# MCU.net
KiCad netlist of a schematic drawn in Altium Designer
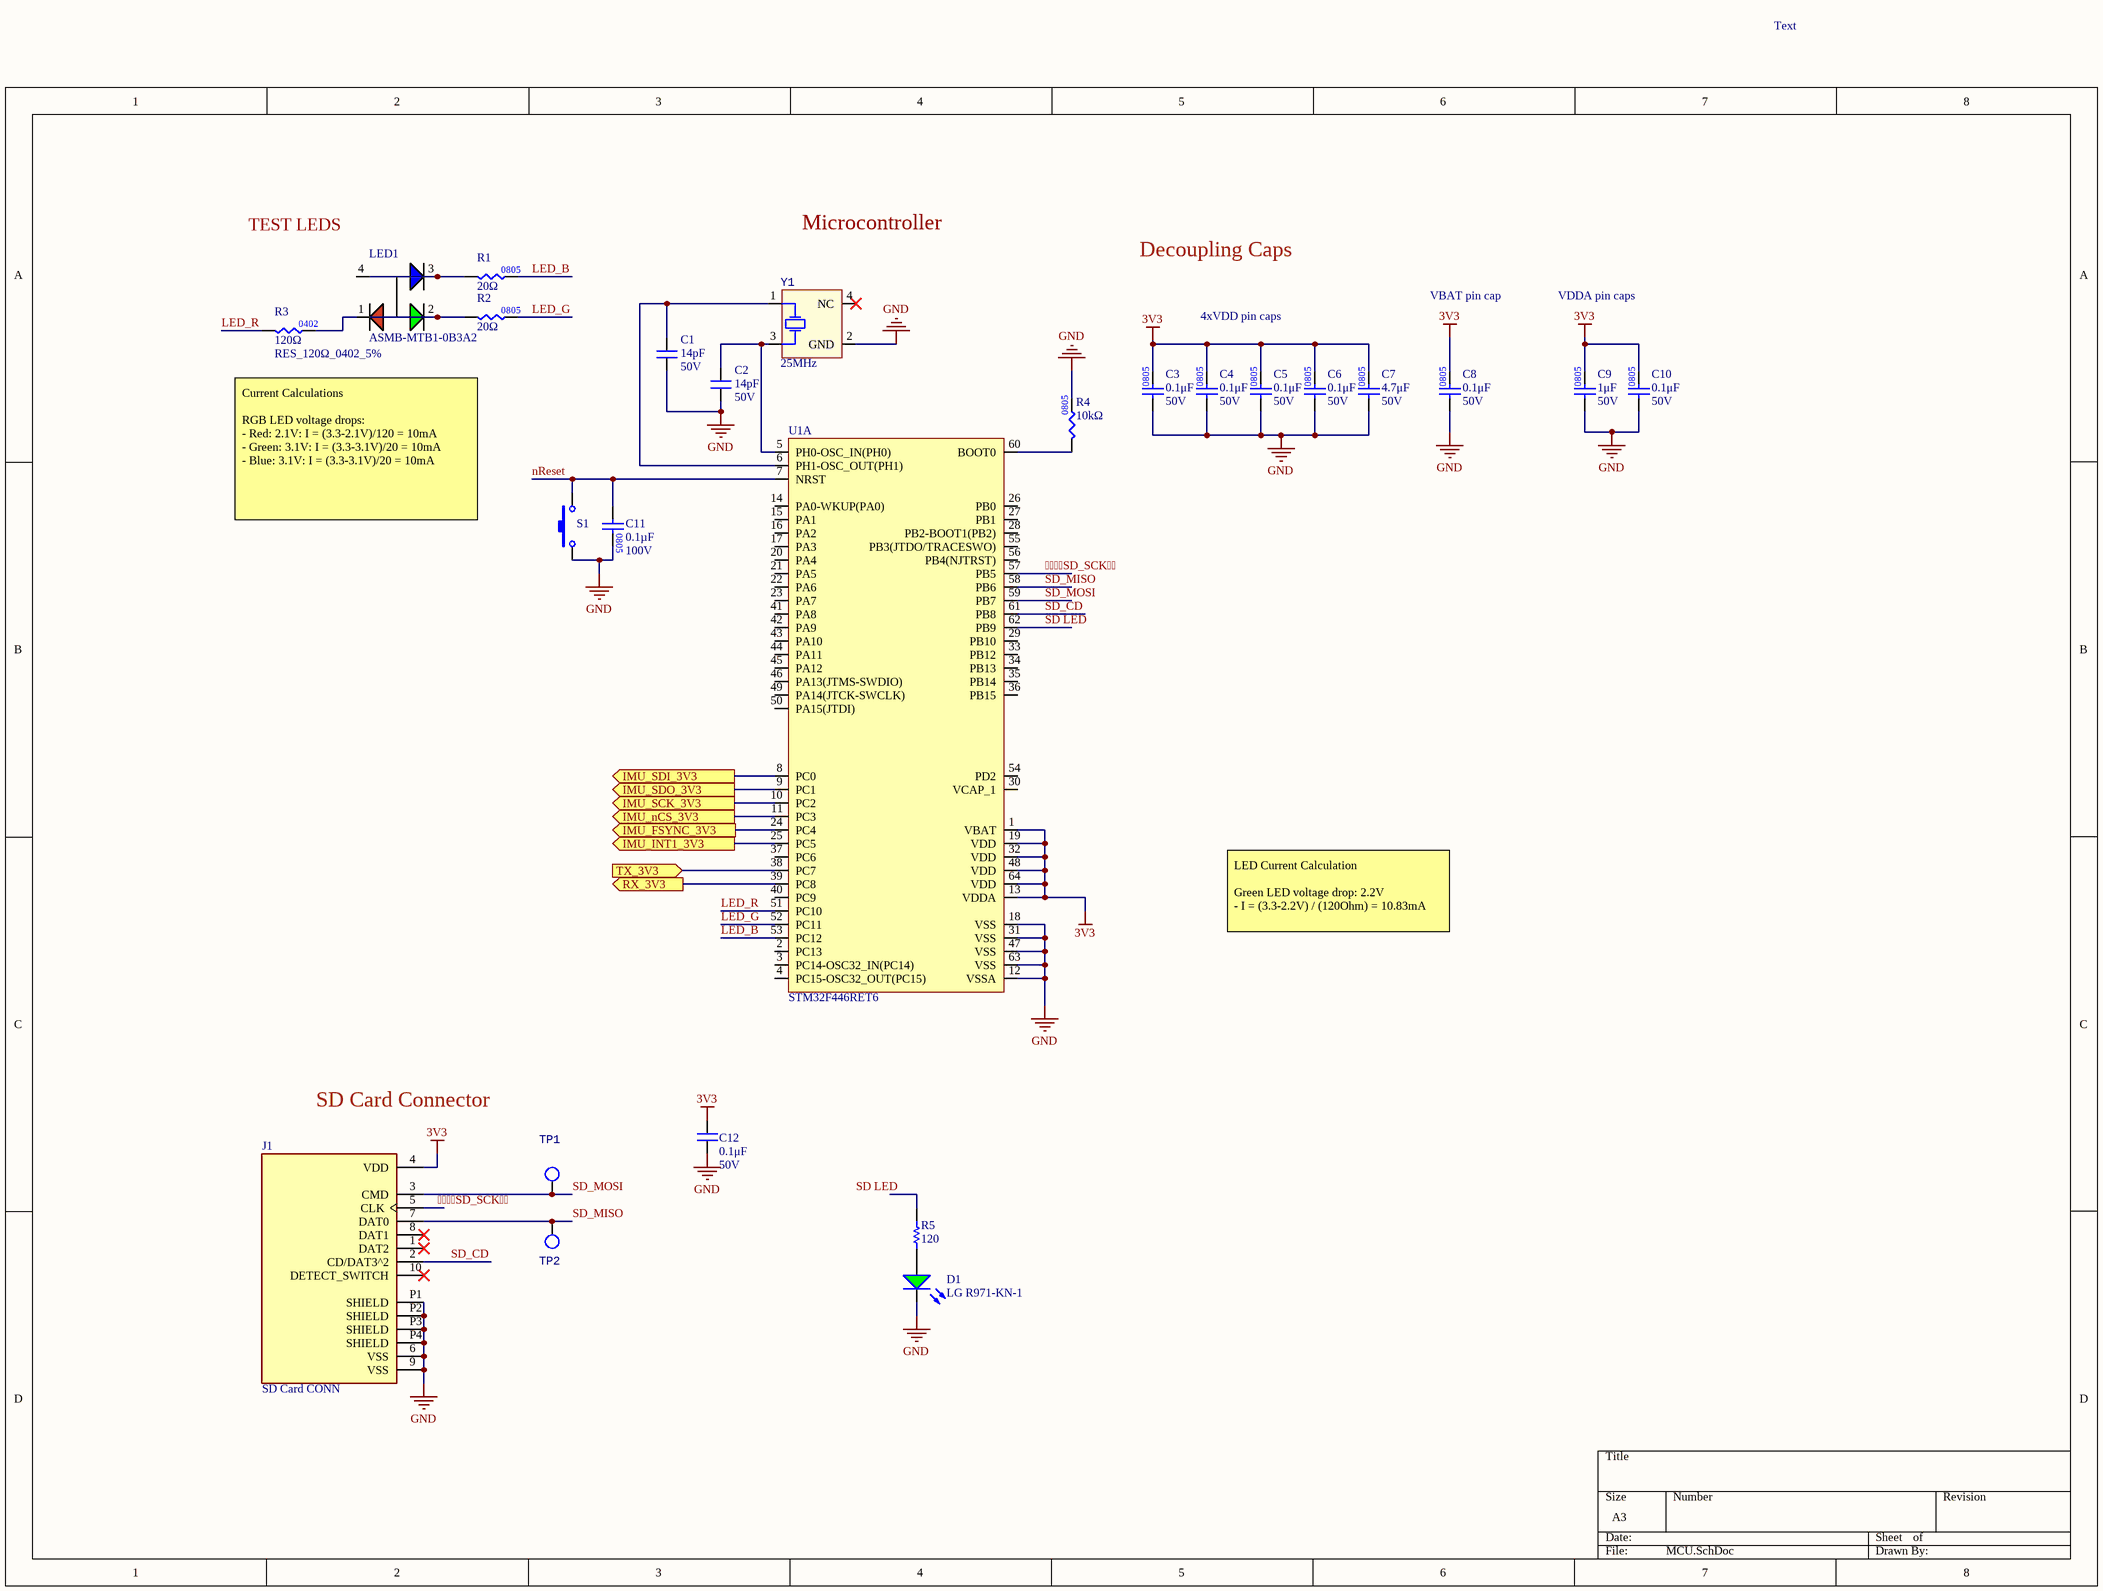
[diagram p0: MCU.SchDoc]

(export (version "E")
  (design (tool "Eeschema 10.0.6"))
  (components
    (comp (ref "C1")
      (value "14pF")
      (footprint "CAPC0603(1608)55_N")
      (description "Cap Ceramic 14pF 50V C0G 5% SMD 0603 125C Cardboard T/R")
      (fields
        (field (name "TOLERANCE") "5%")
        (field (name "VOLTAGE RATING (DC)") "50V")
        (field (name "Comment") "CL10C140JB8NNNC")
      )
      (libsource (lib "UWRT_Schematic_Library_2020") (part "CL10C140JB8NNNC"))
    )
    (comp (ref "C2")
      (value "14pF")
      (footprint "CAPC0603(1608)55_N")
      (description "Cap Ceramic 14pF 50V C0G 5% SMD 0603 125C Cardboard T/R")
      (fields
        (field (name "TOLERANCE") "5%")
        (field (name "VOLTAGE RATING (DC)") "50V")
        (field (name "Comment") "CL10C140JB8NNNC")
      )
      (libsource (lib "UWRT_Schematic_Library_2020") (part "CL10C140JB8NNNC"))
    )
    (comp (ref "C3")
      (value "0.1μF")
      (footprint "CAP0805")
      (description "CAP CER 0.1UF 50V X7R 0805")
      (fields
        (field (name "LCSC PART #") "C49678")
        (field (name "VOLTAGE RATING") "50V")
        (field (name "Comment") "CAP_0.1uF_50V_0805")
      )
      (libsource (lib "UWRT_Schematic_Library_2020") (part "CAP_0.1uF_50V_0805"))
    )
    (comp (ref "C4")
      (value "0.1μF")
      (footprint "CAP0805")
      (description "CAP CER 0.1UF 50V X7R 0805")
      (fields
        (field (name "LCSC PART #") "C49678")
        (field (name "VOLTAGE RATING") "50V")
        (field (name "Comment") "CAP_0.1uF_50V_0805")
      )
      (libsource (lib "UWRT_Schematic_Library_2020") (part "CAP_0.1uF_50V_0805"))
    )
    (comp (ref "C5")
      (value "0.1μF")
      (footprint "CAP0805")
      (description "CAP CER 0.1UF 50V X7R 0805")
      (fields
        (field (name "LCSC PART #") "C49678")
        (field (name "VOLTAGE RATING") "50V")
        (field (name "Comment") "CAP_0.1uF_50V_0805")
      )
      (libsource (lib "UWRT_Schematic_Library_2020") (part "CAP_0.1uF_50V_0805"))
    )
    (comp (ref "C6")
      (value "0.1μF")
      (footprint "CAP0805")
      (description "CAP CER 0.1UF 50V X7R 0805")
      (fields
        (field (name "LCSC PART #") "C49678")
        (field (name "VOLTAGE RATING") "50V")
        (field (name "Comment") "CAP_0.1uF_50V_0805")
      )
      (libsource (lib "UWRT_Schematic_Library_2020") (part "CAP_0.1uF_50V_0805"))
    )
    (comp (ref "C7")
      (value "4.7μF")
      (footprint "CAP0805")
      (description "CAP CER 4.7UF 50V X5R 0805")
      (fields
        (field (name "LCSC PART #") "C1779")
        (field (name "VOLTAGE RATING") "50V")
        (field (name "Comment") "CAP_4.7uF_50V_0805")
      )
      (libsource (lib "UWRT_Schematic_Library_2020") (part "CAP_4.7uF_50V_0805"))
    )
    (comp (ref "C8")
      (value "0.1μF")
      (footprint "CAP0805")
      (description "CAP CER 0.1UF 50V X7R 0805")
      (fields
        (field (name "LCSC PART #") "C49678")
        (field (name "VOLTAGE RATING") "50V")
        (field (name "Comment") "CAP_0.1uF_50V_0805")
      )
      (libsource (lib "UWRT_Schematic_Library_2020") (part "CAP_0.1uF_50V_0805"))
    )
    (comp (ref "C9")
      (value "1μF")
      (footprint "CAP0805")
      (description "CAP CER 1UF 50V X7R 0805")
      (fields
        (field (name "LCSC PART #") "C28323")
        (field (name "VOLTAGE RATING") "50V")
        (field (name "Comment") "CAP_1uF_50V_0805")
      )
      (libsource (lib "UWRT_Schematic_Library_2020") (part "CAP_1uF_50V_0805"))
    )
    (comp (ref "C10")
      (value "0.1μF")
      (footprint "CAP0805")
      (description "CAP CER 0.1UF 50V X7R 0805")
      (fields
        (field (name "LCSC PART #") "C49678")
        (field (name "VOLTAGE RATING") "50V")
        (field (name "Comment") "CAP_0.1uF_50V_0805")
      )
      (libsource (lib "UWRT_Schematic_Library_2020") (part "CAP_0.1uF_50V_0805"))
    )
    (comp (ref "C11")
      (value "0.1µF")
      (footprint "CAP0805")
      (description "CAP CER 0.1UF 100V X7R 0805")
      (fields (field (name "VOLTAGE RATING") "100V") (field (name "Comment") "CAP_0.1uF_100V_0805"))
      (libsource (lib "UWRT_Schematic_Library_2020") (part "CAP_0.1uF_100V_0805"))
    )
    (comp (ref "C12")
      (value "0.1μF")
      (footprint "CAP2012")
      (description "CAP CER 0.1UF 50V X7R 0805")
      (fields
        (field (name "TOLERANCE") "10%")
        (field (name "VOLTAGE RATING") "50V")
        (field (name "Comment") "CAP_0.1uF_50V_0805")
      )
      (libsource (lib "") (part "CAP_0.1uF_50V_0805_1"))
    )
    (comp (ref "D1")
      (value "LG R971-KN-1")
      (footprint "LED_0805_GREEN")
      (description "LED GREEN DIFFUSED 0805 SMD")
      (libsource (lib "UWRT_Schematic_Library_2020") (part "DIO_LED_G"))
    )
    (comp (ref "J1")
      (value "SD Card CONN")
      (footprint "503398-1892")
      (description "12 (9 + 3) Position Card Connector Secure Digital - SD Surface Mount, Right Angle Gold")
      (fields (field (name "MANUFACTURER") "Molex") (field (name "MANUFACTURER PART NUMBER") "503398-1892"))
      (libsource (lib "UWRT_Schematic_Library_2020") (part "SD Card CONN"))
    )
    (comp (ref "LED1")
      (value "LED_RGB")
      (footprint "LED_RGB")
      (description "LED RGB DIFFUSED 4PLCC SMD")
      (fields (field (name "MANUFACTURER PART NUMBER 1") "ASMB-MTB1-0B3A2"))
      (libsource (lib "UWRT_Schematic_Library_2020") (part "LED_RGB"))
    )
    (comp (ref "R1")
      (value "20Ω")
      (footprint "RES0805")
      (description "RES 20 OHM 1% 1/8W 0805")
      (fields (field (name "LCSC PART #") "C17581") (field (name "Comment") "RES_20Ω_0805_1%"))
      (libsource (lib "UWRT_Schematic_Library_2020") (part "RES_20Ω_0805_1%"))
    )
    (comp (ref "R2")
      (value "20Ω")
      (footprint "RES0805")
      (description "RES 20 OHM 1% 1/8W 0805")
      (fields (field (name "LCSC PART #") "C17581") (field (name "Comment") "RES_20Ω_0805_1%"))
      (libsource (lib "UWRT_Schematic_Library_2020") (part "RES_20Ω_0805_1%"))
    )
    (comp (ref "R3")
      (value "RES_120Ω_0402_5%")
      (footprint "RES0402")
      (description "RES 120 OHM 5% 1/16W 0402")
      (fields
        (field (name "POWER") "1/16W")
        (field (name "TOLERANCE") "5%")
        (field (name "ALTIUM_VALUE") "120Ω")
      )
      (libsource (lib "UWRT_Schematic_Library_2020") (part "RES_120Ω_0402_5%"))
    )
    (comp (ref "R4")
      (value "10kΩ")
      (footprint "RES0805")
      (description "RES 10K OHM 5% 1/8W 0805")
      (fields (field (name "LCSC PART #") "C17414") (field (name "Comment") "RES_10kΩ_0805_5%"))
      (libsource (lib "UWRT_Schematic_Library_2020") (part "RES_10kΩ_0805_5%"))
    )
    (comp (ref "R5")
      (value "120")
      (footprint "RESC0603(1608)_N")
      (description "RES SMD 120 OHM 5% 1/10W 0603")
      (fields (field (name "TOLERANCE") "5%") (field (name "Comment") "RES_120R_0603"))
      (libsource (lib "UWRT_Schematic_Library_2020") (part "RES_120R_0603"))
    )
    (comp (ref "S1")
      (value "SW_SPST_NO")
      (footprint "B3U-1000P")
      (description "SMT 3.0 X 2.6 MM TACT SWITCH WIT")
      (libsource (lib "UWRT_Schematic_Library_2020") (part "SW_SPST_NO"))
    )
    (comp (ref "TP1")
      (value "TESTPOINT_LOOP")
      (footprint "TESTPOINT_LOOP")
      (description "PC TEST POINT MINIATURE WHITE")
      (libsource (lib "UWRT_Schematic_Library_2020") (part "TESTPOINT_LOOP"))
    )
    (comp (ref "TP2")
      (value "TESTPOINT_LOOP")
      (footprint "TESTPOINT_LOOP")
      (description "PC TEST POINT MINIATURE WHITE")
      (libsource (lib "UWRT_Schematic_Library_2020") (part "TESTPOINT_LOOP"))
    )
    (comp (ref "U1")
      (value "STM32F446RET6")
      (footprint "UWRT_Footprint_Library_2020:STM_LQFP64_N")
      (description "IC MCU 32BIT 512KB FLASH 64LQFP")
      (libsource (lib "UWRT_Schematic_Library_2020") (part "STM32F446RET6"))
    )
    (comp (ref "Y1")
      (value "CRYSTAL_25MHZ")
      (footprint "SOIC254P1016X440-4N")
      (description "CRYSTAL 25.0000MHZ 12PF SMD")
      (fields (field (name "FREQUENCY") "25MHz"))
      (libsource (lib "UWRT_Schematic_Library_2020") (part "CRYSTAL_25MHZ"))
    )
  )
  (nets
    (net (code "1") (name "/IMU_FSYNC_3V3") (class "Default")
      (node (ref "U1") (pin "24") (pinfunction "PC4_24") (pintype "passive"))
    )
    (net (code "2") (name "/IMU_INT1_3V3") (class "Default")
      (node (ref "U1") (pin "25") (pinfunction "PC5_25") (pintype "passive"))
    )
    (net (code "3") (name "/IMU_SCK_3V3") (class "Default")
      (node (ref "U1") (pin "10") (pinfunction "PC2_10") (pintype "passive"))
    )
    (net (code "4") (name "/IMU_SDI_3V3") (class "Default")
      (node (ref "U1") (pin "8") (pinfunction "PC0_8") (pintype "passive"))
    )
    (net (code "5") (name "/IMU_SDO_3V3") (class "Default")
      (node (ref "U1") (pin "9") (pinfunction "PC1_9") (pintype "passive"))
    )
    (net (code "6") (name "/IMU_nCS_3V3") (class "Default")
      (node (ref "U1") (pin "11") (pinfunction "PC3_11") (pintype "passive"))
    )
    (net (code "7") (name "/RX_3V3") (class "Default")
      (node (ref "U1") (pin "39") (pinfunction "PC8_39") (pintype "passive"))
    )
    (net (code "8") (name "/TX_3V3") (class "Default")
      (node (ref "U1") (pin "38") (pinfunction "PC7_38") (pintype "passive"))
    )
    (net (code "9") (name "3V3") (class "Default")
      (node (ref "C10") (pin "2") (pinfunction "2_2") (pintype "passive"))
      (node (ref "C12") (pin "2") (pinfunction "2_2") (pintype "passive"))
      (node (ref "C3") (pin "2") (pinfunction "2_2") (pintype "passive"))
      (node (ref "C4") (pin "2") (pinfunction "2_2") (pintype "passive"))
      (node (ref "C5") (pin "2") (pinfunction "2_2") (pintype "passive"))
      (node (ref "C6") (pin "2") (pinfunction "2_2") (pintype "passive"))
      (node (ref "C7") (pin "2") (pinfunction "2_2") (pintype "passive"))
      (node (ref "C8") (pin "2") (pinfunction "2_2") (pintype "passive"))
      (node (ref "C9") (pin "2") (pinfunction "2_2") (pintype "passive"))
      (node (ref "J1") (pin "4") (pinfunction "VDD_4") (pintype "power_in"))
      (node (ref "U1") (pin "1") (pinfunction "VBAT_1") (pintype "passive"))
      (node (ref "U1") (pin "13") (pinfunction "VDDA_13") (pintype "passive"))
      (node (ref "U1") (pin "19") (pinfunction "VDD_19") (pintype "passive"))
      (node (ref "U1") (pin "32") (pinfunction "VDD_32") (pintype "passive"))
      (node (ref "U1") (pin "48") (pinfunction "VDD_48") (pintype "passive"))
      (node (ref "U1") (pin "64") (pinfunction "VDD_64") (pintype "passive"))
    )
    (net (code "10") (name "GND") (class "Default")
      (node (ref "C1") (pin "1") (pinfunction "1_1") (pintype "passive"))
      (node (ref "C10") (pin "1") (pinfunction "1_1") (pintype "passive"))
      (node (ref "C11") (pin "2") (pinfunction "2_2") (pintype "passive"))
      (node (ref "C12") (pin "1") (pinfunction "1_1") (pintype "passive"))
      (node (ref "C2") (pin "1") (pinfunction "1_1") (pintype "passive"))
      (node (ref "C3") (pin "1") (pinfunction "1_1") (pintype "passive"))
      (node (ref "C4") (pin "1") (pinfunction "1_1") (pintype "passive"))
      (node (ref "C5") (pin "1") (pinfunction "1_1") (pintype "passive"))
      (node (ref "C6") (pin "1") (pinfunction "1_1") (pintype "passive"))
      (node (ref "C7") (pin "1") (pinfunction "1_1") (pintype "passive"))
      (node (ref "C8") (pin "1") (pinfunction "1_1") (pintype "passive"))
      (node (ref "C9") (pin "1") (pinfunction "1_1") (pintype "passive"))
      (node (ref "D1") (pin "2") (pinfunction "K_2") (pintype "passive"))
      (node (ref "J1") (pin "6") (pinfunction "VSS_6") (pintype "power_in"))
      (node (ref "J1") (pin "9") (pinfunction "VSS_9") (pintype "power_in"))
      (node (ref "J1") (pin "P1") (pinfunction "SHIELD_P1") (pintype "passive"))
      (node (ref "J1") (pin "P2") (pinfunction "SHIELD_P2") (pintype "passive"))
      (node (ref "J1") (pin "P3") (pinfunction "SHIELD_P3") (pintype "passive"))
      (node (ref "J1") (pin "P4") (pinfunction "SHIELD_P4") (pintype "passive"))
      (node (ref "R4") (pin "2") (pinfunction "2_2") (pintype "passive"))
      (node (ref "S1") (pin "1") (pinfunction "1_1") (pintype "passive"))
      (node (ref "U1") (pin "12") (pinfunction "VSSA_12") (pintype "passive"))
      (node (ref "U1") (pin "18") (pinfunction "VSS_18") (pintype "passive"))
      (node (ref "U1") (pin "31") (pinfunction "VSS_31") (pintype "passive"))
      (node (ref "U1") (pin "47") (pinfunction "VSS_47") (pintype "passive"))
      (node (ref "U1") (pin "63") (pinfunction "VSS_63") (pintype "passive"))
      (node (ref "Y1") (pin "2") (pinfunction "GND_2") (pintype "power_in"))
    )
    (net (code "11") (name "Net-(D1-A)") (class "Default")
      (node (ref "D1") (pin "1") (pinfunction "A_1") (pintype "passive"))
      (node (ref "R5") (pin "2") (pinfunction "2_2") (pintype "passive"))
    )
    (net (code "12") (name "Net-(J1-CMD)") (class "Default")
      (node (ref "J1") (pin "3") (pinfunction "CMD_3") (pintype "passive"))
      (node (ref "TP1") (pin "1") (pintype "passive"))
    )
    (net (code "13") (name "Net-(J1-DAT0)") (class "Default")
      (node (ref "J1") (pin "7") (pinfunction "DAT0_7") (pintype "passive"))
      (node (ref "TP2") (pin "1") (pintype "passive"))
    )
    (net (code "14") (name "Net-(LED1-CATHODE_(BLUE))") (class "Default")
      (node (ref "LED1") (pin "3") (pinfunction "CATHODE_(BLUE)_3") (pintype "passive"))
      (node (ref "R1") (pin "1") (pinfunction "1_1") (pintype "passive"))
    )
    (net (code "15") (name "Net-(LED1-CATHODE_(GREEN))") (class "Default")
      (node (ref "LED1") (pin "2") (pinfunction "CATHODE_(GREEN)_2") (pintype "passive"))
      (node (ref "R2") (pin "1") (pinfunction "1_1") (pintype "passive"))
    )
    (net (code "16") (name "Net-(LED1-CATHODE_(RED))") (class "Default")
      (node (ref "LED1") (pin "1") (pinfunction "CATHODE_(RED)_1") (pintype "passive"))
      (node (ref "R3") (pin "2") (pinfunction "2_2") (pintype "passive"))
    )
    (net (code "17") (name "Net-(U1A-BOOT0)") (class "Default")
      (node (ref "R4") (pin "1") (pinfunction "1_1") (pintype "passive"))
      (node (ref "U1") (pin "60") (pinfunction "BOOT0_60") (pintype "passive"))
    )
    (net (code "18") (name "Net-(U1A-NRST)") (class "Default")
      (node (ref "C11") (pin "1") (pinfunction "1_1") (pintype "passive"))
      (node (ref "S1") (pin "2") (pinfunction "2_2") (pintype "passive"))
      (node (ref "U1") (pin "7") (pinfunction "NRST_7") (pintype "passive"))
    )
    (net (code "19") (name "Net-(U1A-PH0-OSC_IN(PH0))") (class "Default")
      (node (ref "C2") (pin "2") (pinfunction "2_2") (pintype "passive"))
      (node (ref "U1") (pin "5") (pinfunction "PH0-OSC_IN(PH0)_5") (pintype "passive"))
      (node (ref "Y1") (pin "3") (pinfunction "HOT_3") (pintype "passive"))
    )
    (net (code "20") (name "Net-(U1A-PH1-OSC_OUT(PH1))") (class "Default")
      (node (ref "C1") (pin "2") (pinfunction "2_2") (pintype "passive"))
      (node (ref "U1") (pin "6") (pinfunction "PH1-OSC_OUT(PH1)_6") (pintype "passive"))
      (node (ref "Y1") (pin "1") (pinfunction "HOT_1") (pintype "passive"))
    )
    (net (code "21") (name "unconnected-(J1-CD{slash}DAT3^2-Pad2)") (class "Default")
      (node (ref "J1") (pin "2") (pinfunction "CD/DAT3^2_2") (pintype "passive"))
    )
    (net (code "22") (name "unconnected-(J1-CLK-Pad5)") (class "Default")
      (node (ref "J1") (pin "5") (pinfunction "CLK_5") (pintype "passive"))
    )
    (net (code "23") (name "unconnected-(J1-DAT1-Pad8)") (class "Default")
      (node (ref "J1") (pin "8") (pinfunction "DAT1_8") (pintype "passive+no_connect"))
    )
    (net (code "24") (name "unconnected-(J1-DAT2-Pad1)") (class "Default")
      (node (ref "J1") (pin "1") (pinfunction "DAT2_1") (pintype "passive+no_connect"))
    )
    (net (code "25") (name "unconnected-(J1-DETECT_SWITCH-Pad10)") (class "Default")
      (node (ref "J1") (pin "10") (pinfunction "DETECT_SWITCH_10") (pintype "passive+no_connect"))
    )
    (net (code "26") (name "unconnected-(LED1-COMMON_ANODE-Pad4)") (class "Default")
      (node (ref "LED1") (pin "4") (pinfunction "COMMON_ANODE_4") (pintype "passive"))
    )
    (net (code "27") (name "unconnected-(R1-Pad2)") (class "Default")
      (node (ref "R1") (pin "2") (pinfunction "2_2") (pintype "passive"))
    )
    (net (code "28") (name "unconnected-(R2-Pad2)") (class "Default")
      (node (ref "R2") (pin "2") (pinfunction "2_2") (pintype "passive"))
    )
    (net (code "29") (name "unconnected-(R3-Pad1)") (class "Default")
      (node (ref "R3") (pin "1") (pinfunction "1_1") (pintype "passive"))
    )
    (net (code "30") (name "unconnected-(R5-Pad1)") (class "Default")
      (node (ref "R5") (pin "1") (pinfunction "1_1") (pintype "passive"))
    )
    (net (code "31") (name "unconnected-(U1A-PA0-WKUP(PA0)-Pad14)") (class "Default")
      (node (ref "U1") (pin "14") (pinfunction "PA0-WKUP(PA0)_14") (pintype "passive"))
    )
    (net (code "32") (name "unconnected-(U1A-PA1-Pad15)") (class "Default")
      (node (ref "U1") (pin "15") (pinfunction "PA1_15") (pintype "passive"))
    )
    (net (code "33") (name "unconnected-(U1A-PA2-Pad16)") (class "Default")
      (node (ref "U1") (pin "16") (pinfunction "PA2_16") (pintype "passive"))
    )
    (net (code "34") (name "unconnected-(U1A-PA3-Pad17)") (class "Default")
      (node (ref "U1") (pin "17") (pinfunction "PA3_17") (pintype "passive"))
    )
    (net (code "35") (name "unconnected-(U1A-PA4-Pad20)") (class "Default")
      (node (ref "U1") (pin "20") (pinfunction "PA4_20") (pintype "passive"))
    )
    (net (code "36") (name "unconnected-(U1A-PA5-Pad21)") (class "Default")
      (node (ref "U1") (pin "21") (pinfunction "PA5_21") (pintype "passive"))
    )
    (net (code "37") (name "unconnected-(U1A-PA6-Pad22)") (class "Default")
      (node (ref "U1") (pin "22") (pinfunction "PA6_22") (pintype "passive"))
    )
    (net (code "38") (name "unconnected-(U1A-PA7-Pad23)") (class "Default")
      (node (ref "U1") (pin "23") (pinfunction "PA7_23") (pintype "passive"))
    )
    (net (code "39") (name "unconnected-(U1A-PA8-Pad41)") (class "Default")
      (node (ref "U1") (pin "41") (pinfunction "PA8_41") (pintype "passive"))
    )
    (net (code "40") (name "unconnected-(U1A-PA9-Pad42)") (class "Default")
      (node (ref "U1") (pin "42") (pinfunction "PA9_42") (pintype "passive"))
    )
    (net (code "41") (name "unconnected-(U1A-PA10-Pad43)") (class "Default")
      (node (ref "U1") (pin "43") (pinfunction "PA10_43") (pintype "passive"))
    )
    (net (code "42") (name "unconnected-(U1A-PA11-Pad44)") (class "Default")
      (node (ref "U1") (pin "44") (pinfunction "PA11_44") (pintype "passive"))
    )
    (net (code "43") (name "unconnected-(U1A-PA12-Pad45)") (class "Default")
      (node (ref "U1") (pin "45") (pinfunction "PA12_45") (pintype "passive"))
    )
    (net (code "44") (name "unconnected-(U1A-PA13(JTMS-SWDIO)-Pad46)") (class "Default")
      (node (ref "U1") (pin "46") (pinfunction "PA13(JTMS-SWDIO)_46") (pintype "passive"))
    )
    (net (code "45") (name "unconnected-(U1A-PA14(JTCK-SWCLK)-Pad49)") (class "Default")
      (node (ref "U1") (pin "49") (pinfunction "PA14(JTCK-SWCLK)_49") (pintype "passive"))
    )
    (net (code "46") (name "unconnected-(U1A-PA15(JTDI)-Pad50)") (class "Default")
      (node (ref "U1") (pin "50") (pinfunction "PA15(JTDI)_50") (pintype "passive"))
    )
    (net (code "47") (name "unconnected-(U1A-PB0-Pad26)") (class "Default")
      (node (ref "U1") (pin "26") (pinfunction "PB0_26") (pintype "passive"))
    )
    (net (code "48") (name "unconnected-(U1A-PB1-Pad27)") (class "Default")
      (node (ref "U1") (pin "27") (pinfunction "PB1_27") (pintype "passive"))
    )
    (net (code "49") (name "unconnected-(U1A-PB2-BOOT1(PB2)-Pad28)") (class "Default")
      (node (ref "U1") (pin "28") (pinfunction "PB2-BOOT1(PB2)_28") (pintype "passive"))
    )
    (net (code "50") (name "unconnected-(U1A-PB3(JTDO{slash}TRACESWO)-Pad55)") (class "Default")
      (node (ref "U1") (pin "55") (pinfunction "PB3(JTDO/TRACESWO)_55") (pintype "passive"))
    )
    (net (code "51") (name "unconnected-(U1A-PB4(NJTRST)-Pad56)") (class "Default")
      (node (ref "U1") (pin "56") (pinfunction "PB4(NJTRST)_56") (pintype "passive"))
    )
    (net (code "52") (name "unconnected-(U1A-PB5-Pad57)") (class "Default")
      (node (ref "U1") (pin "57") (pinfunction "PB5_57") (pintype "passive"))
    )
    (net (code "53") (name "unconnected-(U1A-PB6-Pad58)") (class "Default")
      (node (ref "U1") (pin "58") (pinfunction "PB6_58") (pintype "passive"))
    )
    (net (code "54") (name "unconnected-(U1A-PB7-Pad59)") (class "Default")
      (node (ref "U1") (pin "59") (pinfunction "PB7_59") (pintype "passive"))
    )
    (net (code "55") (name "unconnected-(U1A-PB8-Pad61)") (class "Default")
      (node (ref "U1") (pin "61") (pinfunction "PB8_61") (pintype "passive"))
    )
    (net (code "56") (name "unconnected-(U1A-PB9-Pad62)") (class "Default")
      (node (ref "U1") (pin "62") (pinfunction "PB9_62") (pintype "passive"))
    )
    (net (code "57") (name "unconnected-(U1A-PB10-Pad29)") (class "Default")
      (node (ref "U1") (pin "29") (pinfunction "PB10_29") (pintype "passive"))
    )
    (net (code "58") (name "unconnected-(U1A-PB12-Pad33)") (class "Default")
      (node (ref "U1") (pin "33") (pinfunction "PB12_33") (pintype "passive"))
    )
    (net (code "59") (name "unconnected-(U1A-PB13-Pad34)") (class "Default")
      (node (ref "U1") (pin "34") (pinfunction "PB13_34") (pintype "passive"))
    )
    (net (code "60") (name "unconnected-(U1A-PB14-Pad35)") (class "Default")
      (node (ref "U1") (pin "35") (pinfunction "PB14_35") (pintype "passive"))
    )
    (net (code "61") (name "unconnected-(U1A-PB15-Pad36)") (class "Default")
      (node (ref "U1") (pin "36") (pinfunction "PB15_36") (pintype "passive"))
    )
    (net (code "62") (name "unconnected-(U1A-PC6-Pad37)") (class "Default")
      (node (ref "U1") (pin "37") (pinfunction "PC6_37") (pintype "passive"))
    )
    (net (code "63") (name "unconnected-(U1A-PC9-Pad40)") (class "Default")
      (node (ref "U1") (pin "40") (pinfunction "PC9_40") (pintype "passive"))
    )
    (net (code "64") (name "unconnected-(U1A-PC10-Pad51)") (class "Default")
      (node (ref "U1") (pin "51") (pinfunction "PC10_51") (pintype "passive"))
    )
    (net (code "65") (name "unconnected-(U1A-PC11-Pad52)") (class "Default")
      (node (ref "U1") (pin "52") (pinfunction "PC11_52") (pintype "passive"))
    )
    (net (code "66") (name "unconnected-(U1A-PC12-Pad53)") (class "Default")
      (node (ref "U1") (pin "53") (pinfunction "PC12_53") (pintype "passive"))
    )
    (net (code "67") (name "unconnected-(U1A-PC13-Pad2)") (class "Default")
      (node (ref "U1") (pin "2") (pinfunction "PC13_2") (pintype "passive"))
    )
    (net (code "68") (name "unconnected-(U1A-PC14-OSC32_IN(PC14)-Pad3)") (class "Default")
      (node (ref "U1") (pin "3") (pinfunction "PC14-OSC32_IN(PC14)_3") (pintype "passive"))
    )
    (net (code "69") (name "unconnected-(U1A-PC15-OSC32_OUT(PC15)-Pad4)") (class "Default")
      (node (ref "U1") (pin "4") (pinfunction "PC15-OSC32_OUT(PC15)_4") (pintype "passive"))
    )
    (net (code "70") (name "unconnected-(U1A-PD2-Pad54)") (class "Default")
      (node (ref "U1") (pin "54") (pinfunction "PD2_54") (pintype "passive"))
    )
    (net (code "71") (name "unconnected-(U1A-VCAP_1-Pad30)") (class "Default")
      (node (ref "U1") (pin "30") (pinfunction "VCAP_1_30") (pintype "passive"))
    )
    (net (code "72") (name "unconnected-(Y1-NC-Pad4)") (class "Default")
      (node (ref "Y1") (pin "4") (pinfunction "NC_4") (pintype "passive+no_connect"))
    )
  )
)
